# bigben.net
KiCad netlist of a schematic drawn in EAGLE
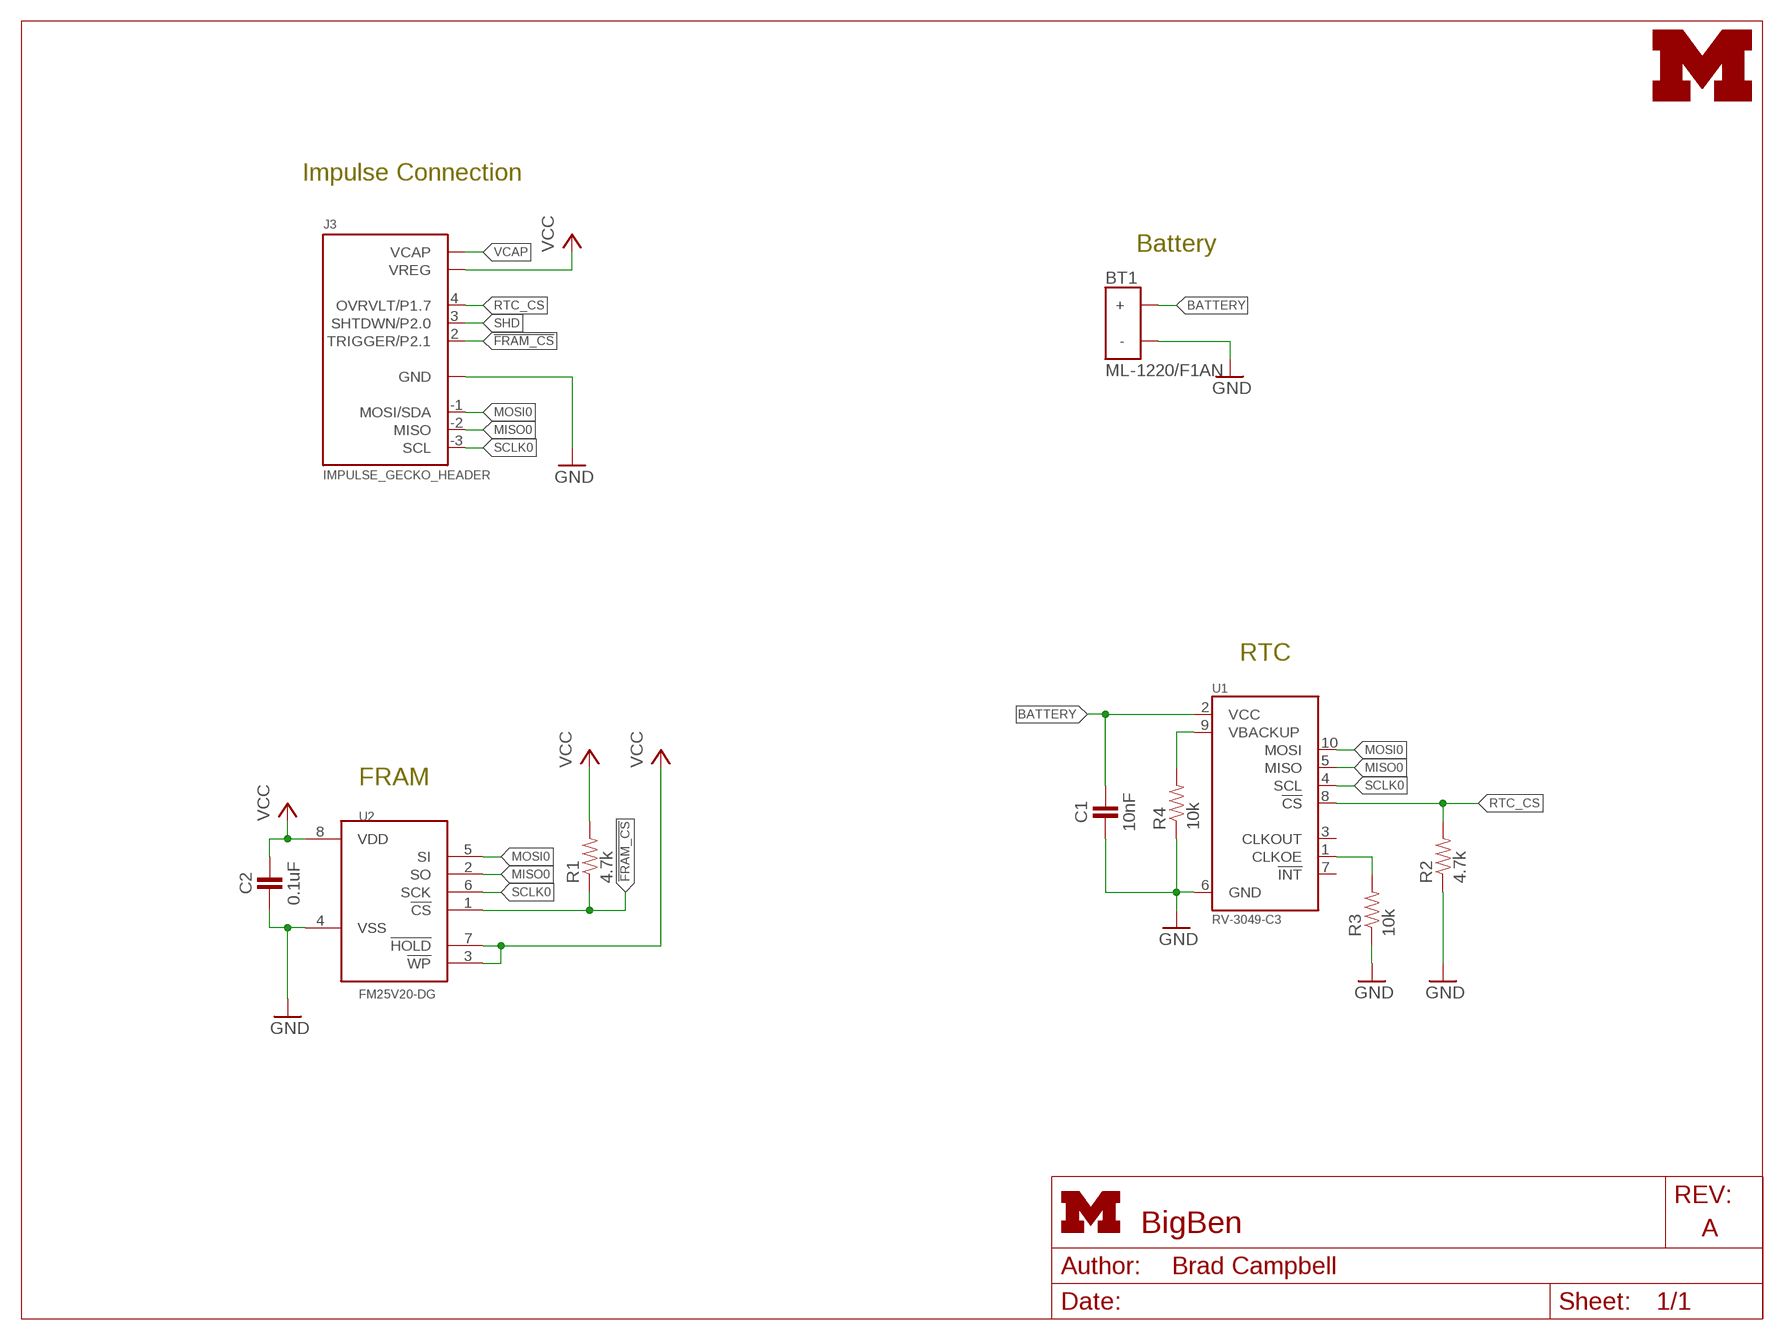
[diagram p0: schematic, sheet 1]

(export (version "E")
  (design (tool "Eeschema 10.0.6"))
  (components
    (comp (ref "BT1")
      (value "ML-1220/F1AN")
      (footprint "eagle-import:ML-1220_F1BN")
      (libsource (lib "eagle-import") (part "ML-1220/F1AN"))
    )
    (comp (ref "C1")
      (value "10nF")
      (footprint "eagle-import:0402_CAP")
      (libsource (lib "eagle-import") (part "CAPACITOR"))
    )
    (comp (ref "C2")
      (value "0.1uF")
      (footprint "eagle-import:0402_CAP")
      (libsource (lib "eagle-import") (part "CAPACITOR"))
    )
    (comp (ref "J3")
      (value "IMPULSE_GECKO_HEADER")
      (footprint "eagle-import:HEADER1X9_0.05IN")
      (libsource (lib "eagle-import") (part "IMPULSE_GECKO_HEADER"))
    )
    (comp (ref "LOGO1")
      (value "UMICH_SOLID_TINY")
      (footprint "eagle-import:UMICH_SOLID_50MIL")
      (libsource (lib "eagle-import") (part "UMICH_SOLID_TINY"))
    )
    (comp (ref "R1")
      (value "4.7k")
      (footprint "eagle-import:0402_RES")
      (libsource (lib "eagle-import") (part "RESISTOR"))
    )
    (comp (ref "R2")
      (value "4.7k")
      (footprint "eagle-import:0402_RES")
      (libsource (lib "eagle-import") (part "RESISTOR"))
    )
    (comp (ref "R3")
      (value "10k")
      (footprint "eagle-import:0402_RES")
      (libsource (lib "eagle-import") (part "RESISTOR"))
    )
    (comp (ref "R4")
      (value "10k")
      (footprint "eagle-import:0402_RES")
      (libsource (lib "eagle-import") (part "RESISTOR"))
    )
    (comp (ref "U1")
      (value "RV-3049-C3")
      (footprint "eagle-import:MICRO-CRYSTAL-C3")
      (libsource (lib "eagle-import") (part "RV-3049-C3"))
    )
    (comp (ref "U2")
      (value "FM25V20-DG")
      (footprint "eagle-import:TDFN-8_6MM")
      (libsource (lib "eagle-import") (part "FM25V20-DG"))
    )
  )
  (nets
    (net (code "1") (name "/~{FRAM_CS}") (class "Default")
      (node (ref "J3") (pin "2") (pinfunction "TRIGGER/P2.1_2") (pintype "bidirectional"))
      (node (ref "R1") (pin "1") (pinfunction "1_1") (pintype "passive"))
      (node (ref "U2") (pin "1") (pinfunction "~{CS}_1") (pintype "bidirectional"))
    )
    (net (code "2") (name "BATTERY") (class "Default")
      (node (ref "BT1") (pin "POS") (pinfunction "+_POS") (pintype "bidirectional"))
      (node (ref "C1") (pin "1") (pinfunction "1_1") (pintype "bidirectional"))
      (node (ref "U1") (pin "2") (pinfunction "VCC_2") (pintype "bidirectional"))
    )
    (net (code "3") (name "GND") (class "Default")
      (node (ref "BT1") (pin "NEG") (pinfunction "-_NEG") (pintype "bidirectional"))
      (node (ref "C1") (pin "2") (pinfunction "2_2") (pintype "bidirectional"))
      (node (ref "C2") (pin "2") (pinfunction "2_2") (pintype "bidirectional"))
      (node (ref "J3") (pin "0") (pinfunction "GND_0") (pintype "bidirectional"))
      (node (ref "R2") (pin "1") (pinfunction "1_1") (pintype "passive"))
      (node (ref "R3") (pin "1") (pinfunction "1_1") (pintype "passive"))
      (node (ref "R4") (pin "1") (pinfunction "1_1") (pintype "passive"))
      (node (ref "U1") (pin "6") (pinfunction "GND_6") (pintype "bidirectional"))
      (node (ref "U2") (pin "4") (pinfunction "VSS_4") (pintype "bidirectional"))
    )
    (net (code "4") (name "MISO0") (class "Default")
      (node (ref "J3") (pin "-2") (pinfunction "MISO_-2") (pintype "bidirectional"))
      (node (ref "U1") (pin "5") (pinfunction "MISO_5") (pintype "bidirectional"))
      (node (ref "U2") (pin "2") (pinfunction "SO_2") (pintype "bidirectional"))
    )
    (net (code "5") (name "MOSI0") (class "Default")
      (node (ref "J3") (pin "-1") (pinfunction "MOSI/SDA_-1") (pintype "bidirectional"))
      (node (ref "U1") (pin "10") (pinfunction "MOSI_10") (pintype "bidirectional"))
      (node (ref "U2") (pin "5") (pinfunction "SI_5") (pintype "bidirectional"))
    )
    (net (code "6") (name "Net-(U1-CLKOE)") (class "Default")
      (node (ref "R3") (pin "2") (pinfunction "2_2") (pintype "passive"))
      (node (ref "U1") (pin "1") (pinfunction "CLKOE_1") (pintype "bidirectional"))
    )
    (net (code "7") (name "Net-(U1-VBACKUP)") (class "Default")
      (node (ref "R4") (pin "2") (pinfunction "2_2") (pintype "passive"))
      (node (ref "U1") (pin "9") (pinfunction "VBACKUP_9") (pintype "bidirectional"))
    )
    (net (code "8") (name "RTC_CS") (class "Default")
      (node (ref "J3") (pin "4") (pinfunction "OVRVLT/P1.7_4") (pintype "bidirectional"))
      (node (ref "R2") (pin "2") (pinfunction "2_2") (pintype "passive"))
      (node (ref "U1") (pin "8") (pinfunction "~{CS}_8") (pintype "bidirectional"))
    )
    (net (code "9") (name "SCLK0") (class "Default")
      (node (ref "J3") (pin "-3") (pinfunction "SCL_-3") (pintype "bidirectional"))
      (node (ref "U1") (pin "4") (pinfunction "SCL_4") (pintype "bidirectional"))
      (node (ref "U2") (pin "6") (pinfunction "SCK_6") (pintype "bidirectional"))
    )
    (net (code "10") (name "SHD") (class "Default")
      (node (ref "J3") (pin "3") (pinfunction "SHTDWN/P2.0_3") (pintype "bidirectional"))
    )
    (net (code "11") (name "VCAP") (class "Default")
      (node (ref "J3") (pin "5") (pinfunction "VCAP_5") (pintype "output"))
    )
    (net (code "12") (name "VCC") (class "Default")
      (node (ref "C2") (pin "1") (pinfunction "1_1") (pintype "bidirectional"))
      (node (ref "J3") (pin "1") (pinfunction "VREG_1") (pintype "bidirectional"))
      (node (ref "R1") (pin "2") (pinfunction "2_2") (pintype "passive"))
      (node (ref "U2") (pin "3") (pinfunction "~{WP}_3") (pintype "bidirectional"))
      (node (ref "U2") (pin "7") (pinfunction "~{HOLD}_7") (pintype "bidirectional"))
      (node (ref "U2") (pin "8") (pinfunction "VDD_8") (pintype "bidirectional"))
    )
    (net (code "13") (name "unconnected-(U1-CLKOUT-Pad3)") (class "Default")
      (node (ref "U1") (pin "3") (pinfunction "CLKOUT_3") (pintype "bidirectional"))
    )
    (net (code "14") (name "unconnected-(U1-~{INT}-Pad7)") (class "Default")
      (node (ref "U1") (pin "7") (pinfunction "~{INT}_7") (pintype "bidirectional"))
    )
  )
)
